# PC_PS2_NB2IND02.net
KiCad netlist of a schematic drawn in Altium Designer
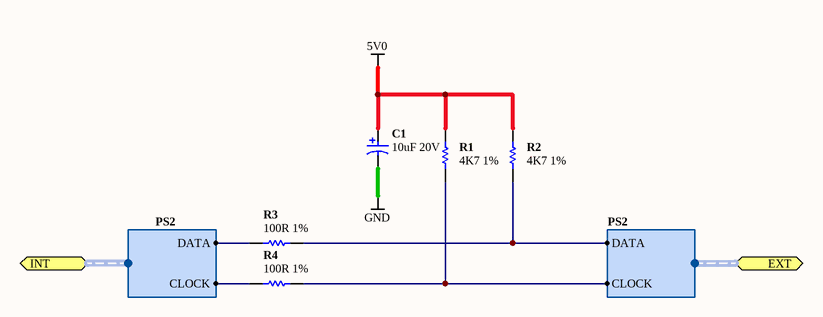
[diagram p0: PC_PS2_NB2IND02.SchDoc]

(export (version "E")
  (design (tool "Eeschema 10.0.6"))
  (components
    (comp (ref "C1")
      (value "10uF 20V")
      (footprint "CAPC3528-STAR")
      (description "Capacitor, Tantalum, 10uF 10% 20V MCCT-B (3528)")
      (fields (field (name "TOLERANCE") "10 %"))
      (libsource (lib "altium-import") (part "root_0_CAP-P_"))
    )
    (comp (ref "R1")
      (value "4K7 1%")
      (footprint "RESC1005-STAR")
      (description "Resistor, 4K7 1% 0402 (1005)")
      (fields (field (name "TOLERANCE") "1 %"))
      (libsource (lib "altium-import") (part "root_0_RES_"))
    )
    (comp (ref "R2")
      (value "4K7 1%")
      (footprint "RESC1005-STAR")
      (description "Resistor, 4K7 1% 0402 (1005)")
      (fields (field (name "TOLERANCE") "1 %"))
      (libsource (lib "altium-import") (part "root_0_RES_"))
    )
    (comp (ref "R3")
      (value "100R 1%")
      (footprint "RESC1005-STAR")
      (description "Resistor, 100R 1% 0402 (1005)")
      (fields (field (name "TOLERANCE") "1 %"))
      (libsource (lib "altium-import") (part "root_1_RES_"))
    )
    (comp (ref "R4")
      (value "100R 1%")
      (footprint "RESC1005-STAR")
      (description "Resistor, 100R 1% 0402 (1005)")
      (fields (field (name "TOLERANCE") "1 %"))
      (libsource (lib "altium-import") (part "root_1_RES_"))
    )
  )
  (nets
    (net (code "3") (name "5V0") (class "Default")
      (node (ref "C1") (pin "1") (pinfunction "1_1") (pintype "passive"))
      (node (ref "R1") (pin "1") (pinfunction "1_1") (pintype "passive"))
      (node (ref "R2") (pin "1") (pinfunction "1_1") (pintype "passive"))
    )
    (net (code "4") (name "GND") (class "Default")
      (node (ref "C1") (pin "2") (pinfunction "2_2") (pintype "passive"))
    )
    (net (code "5") (name "Net-(R1-Pad2)") (class "Default")
      (node (ref "R1") (pin "2") (pinfunction "2_2") (pintype "passive"))
      (node (ref "R4") (pin "2") (pinfunction "2_2") (pintype "passive"))
    )
    (net (code "6") (name "Net-(R2-Pad2)") (class "Default")
      (node (ref "R2") (pin "2") (pinfunction "2_2") (pintype "passive"))
      (node (ref "R3") (pin "2") (pinfunction "2_2") (pintype "passive"))
    )
    (net (code "7") (name "unconnected-(R3-Pad1)") (class "Default")
      (node (ref "R3") (pin "1") (pinfunction "1_1") (pintype "passive"))
    )
    (net (code "8") (name "unconnected-(R4-Pad1)") (class "Default")
      (node (ref "R4") (pin "1") (pinfunction "1_1") (pintype "passive"))
    )
  )
)
